# WS2811Controller.net
KiCad netlist of a schematic drawn in EAGLE
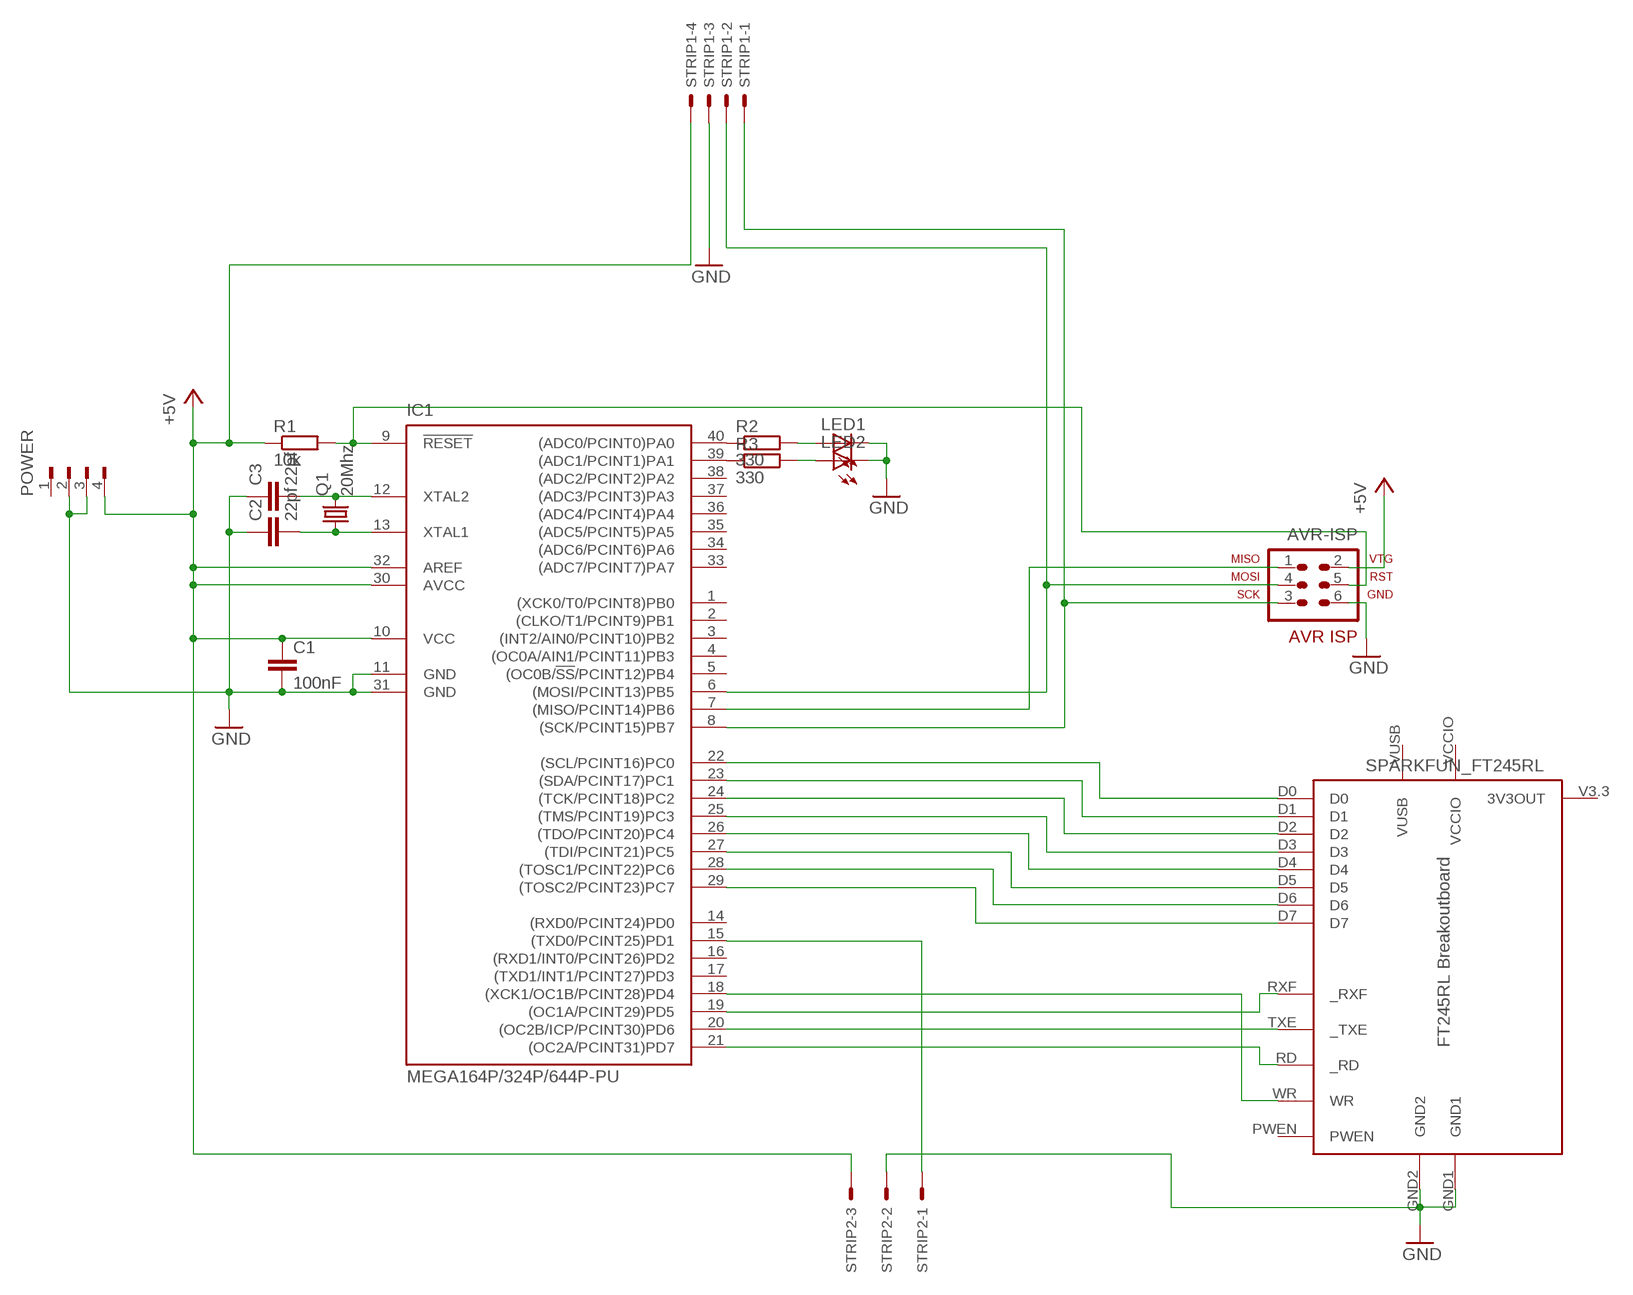
[diagram p0: schematic, sheet 1]

(export (version "E")
  (design (tool "Eeschema 10.0.6"))
  (components
    (comp (ref "AVR-ISP")
      (value "AVR-ISP-6")
      (footprint "eagle-import:AVR-ISP-6")
      (libsource (lib "eagle-import") (part "AVR-ISP-6"))
    )
    (comp (ref "C1")
      (value "100nF")
      (footprint "eagle-import:C050-030X075")
      (libsource (lib "eagle-import") (part "C-EU050-030X075"))
    )
    (comp (ref "C2")
      (value "22pf")
      (footprint "eagle-import:C050-024X044")
      (libsource (lib "eagle-import") (part "C-EU050-024X044"))
    )
    (comp (ref "C3")
      (value "22pf")
      (footprint "eagle-import:C050-024X044")
      (libsource (lib "eagle-import") (part "C-EU050-024X044"))
    )
    (comp (ref "IC1")
      (value "MEGA164P/324P/644P-PU")
      (footprint "eagle-import:DIL40")
      (libsource (lib "eagle-import") (part "MEGA164P/324P/644P-PU"))
    )
    (comp (ref "LED1")
      (value "LED3MM")
      (footprint "eagle-import:LED3MM")
      (libsource (lib "eagle-import") (part "LED3MM"))
    )
    (comp (ref "LED2")
      (value "LED3MM")
      (footprint "eagle-import:LED3MM")
      (libsource (lib "eagle-import") (part "LED3MM"))
    )
    (comp (ref "POWER")
      (value "FLOPPY-4901")
      (footprint "eagle-import:827001")
      (libsource (lib "eagle-import") (part "FLOPPY-4901"))
    )
    (comp (ref "Q1")
      (value "20Mhz")
      (footprint "eagle-import:HC49U70")
      (libsource (lib "eagle-import") (part "CRYSTALHC49U70"))
    )
    (comp (ref "R1")
      (value "10k")
      (footprint "eagle-import:0207_10")
      (libsource (lib "eagle-import") (part "R-EU_0207/10"))
    )
    (comp (ref "R2")
      (value "330")
      (footprint "eagle-import:0207_10")
      (libsource (lib "eagle-import") (part "R-EU_0207/10"))
    )
    (comp (ref "R3")
      (value "330")
      (footprint "eagle-import:0207_10")
      (libsource (lib "eagle-import") (part "R-EU_0207/10"))
    )
    (comp (ref "SPARKFUN_FT245RL")
      (value "FT245RL_BREAKOUTBOARD")
      (footprint "eagle-import:SPARKFUN_FT245RL_BOARD")
      (libsource (lib "eagle-import") (part "FT245RL_BREAKOUTBOARD"))
    )
    (comp (ref "STRIP1")
      (value "22-27-2041-04")
      (footprint "eagle-import:6410-04")
      (libsource (lib "eagle-import") (part "22-?-0427-2041"))
    )
    (comp (ref "STRIP2")
      (value "22-27-2031-03")
      (footprint "eagle-import:6410-03")
      (libsource (lib "eagle-import") (part "22-?-0327-2031"))
    )
  )
  (nets
    (net (code "1") (name "+5V") (class "Default")
      (node (ref "AVR-ISP") (pin "2") (pinfunction "2_2") (pintype "passive"))
      (node (ref "C1") (pin "1") (pinfunction "1_1") (pintype "passive"))
      (node (ref "IC1") (pin "10") (pinfunction "VCC_10") (pintype "power_in"))
      (node (ref "IC1") (pin "30") (pinfunction "AVCC_30") (pintype "power_in"))
      (node (ref "IC1") (pin "32") (pinfunction "AREF_32") (pintype "power_in"))
      (node (ref "POWER") (pin "4") (pinfunction "4_4") (pintype "passive"))
      (node (ref "R1") (pin "1") (pinfunction "1_1") (pintype "passive"))
      (node (ref "STRIP1") (pin "4") (pinfunction "S_4") (pintype "passive"))
      (node (ref "STRIP2") (pin "3") (pinfunction "S_3") (pintype "passive"))
    )
    (net (code "2") (name "/VCCIO") (class "Default")
      (node (ref "SPARKFUN_FT245RL") (pin "VCCIO") (pinfunction "VCCIO_VCCIO") (pintype "power_in"))
    )
    (net (code "3") (name "GND") (class "Default")
      (node (ref "AVR-ISP") (pin "6") (pinfunction "6_6") (pintype "passive"))
      (node (ref "C1") (pin "2") (pinfunction "2_2") (pintype "passive"))
      (node (ref "C2") (pin "1") (pinfunction "1_1") (pintype "passive"))
      (node (ref "C3") (pin "1") (pinfunction "1_1") (pintype "passive"))
      (node (ref "IC1") (pin "11") (pinfunction "GND_11") (pintype "power_in"))
      (node (ref "IC1") (pin "31") (pinfunction "GND_31") (pintype "power_in"))
      (node (ref "LED1") (pin "K") (pinfunction "C_K") (pintype "passive"))
      (node (ref "LED2") (pin "K") (pinfunction "C_K") (pintype "passive"))
      (node (ref "POWER") (pin "2") (pinfunction "2_2") (pintype "passive"))
      (node (ref "POWER") (pin "3") (pinfunction "3_3") (pintype "passive"))
      (node (ref "SPARKFUN_FT245RL") (pin "GND1") (pinfunction "GND1_GND1") (pintype "power_in"))
      (node (ref "SPARKFUN_FT245RL") (pin "GND2") (pinfunction "GND2_GND2") (pintype "power_in"))
      (node (ref "STRIP1") (pin "3") (pinfunction "S_3") (pintype "passive"))
      (node (ref "STRIP2") (pin "2") (pinfunction "S_2") (pintype "passive"))
    )
    (net (code "4") (name "Net-(IC1-(ADC0{slash}PCINT0)PA0)") (class "Default")
      (node (ref "IC1") (pin "40") (pinfunction "(ADC0/PCINT0)PA0_40") (pintype "bidirectional"))
      (node (ref "R2") (pin "1") (pinfunction "1_1") (pintype "passive"))
    )
    (net (code "5") (name "Net-(IC1-(ADC1{slash}PCINT1)PA1)") (class "Default")
      (node (ref "IC1") (pin "39") (pinfunction "(ADC1/PCINT1)PA1_39") (pintype "bidirectional"))
      (node (ref "R3") (pin "1") (pinfunction "1_1") (pintype "passive"))
    )
    (net (code "6") (name "Net-(IC1-(MISO{slash}PCINT14)PB6)") (class "Default")
      (node (ref "AVR-ISP") (pin "1") (pinfunction "1_1") (pintype "passive"))
      (node (ref "IC1") (pin "7") (pinfunction "(MISO/PCINT14)PB6_7") (pintype "bidirectional"))
    )
    (net (code "7") (name "Net-(IC1-(MOSI{slash}PCINT13)PB5)") (class "Default")
      (node (ref "AVR-ISP") (pin "4") (pinfunction "4_4") (pintype "passive"))
      (node (ref "IC1") (pin "6") (pinfunction "(MOSI/PCINT13)PB5_6") (pintype "bidirectional"))
      (node (ref "STRIP1") (pin "2") (pinfunction "S_2") (pintype "passive"))
    )
    (net (code "8") (name "Net-(IC1-(OC1A{slash}PCINT29)PD5)") (class "Default")
      (node (ref "IC1") (pin "19") (pinfunction "(OC1A/PCINT29)PD5_19") (pintype "bidirectional"))
      (node (ref "SPARKFUN_FT245RL") (pin "RXF") (pinfunction "_RXF_RXF") (pintype "bidirectional"))
    )
    (net (code "9") (name "Net-(IC1-(OC2A{slash}PCINT31)PD7)") (class "Default")
      (node (ref "IC1") (pin "21") (pinfunction "(OC2A/PCINT31)PD7_21") (pintype "bidirectional"))
      (node (ref "SPARKFUN_FT245RL") (pin "RD") (pinfunction "_RD_RD") (pintype "bidirectional"))
    )
    (net (code "10") (name "Net-(IC1-(OC2B{slash}ICP{slash}PCINT30)PD6)") (class "Default")
      (node (ref "IC1") (pin "20") (pinfunction "(OC2B/ICP/PCINT30)PD6_20") (pintype "bidirectional"))
      (node (ref "SPARKFUN_FT245RL") (pin "TXE") (pinfunction "_TXE_TXE") (pintype "bidirectional"))
    )
    (net (code "11") (name "Net-(IC1-(SCK{slash}PCINT15)PB7)") (class "Default")
      (node (ref "AVR-ISP") (pin "3") (pinfunction "3_3") (pintype "passive"))
      (node (ref "IC1") (pin "8") (pinfunction "(SCK/PCINT15)PB7_8") (pintype "bidirectional"))
      (node (ref "STRIP1") (pin "1") (pinfunction "S_1") (pintype "passive"))
    )
    (net (code "12") (name "Net-(IC1-(SCL{slash}PCINT16)PC0)") (class "Default")
      (node (ref "IC1") (pin "22") (pinfunction "(SCL/PCINT16)PC0_22") (pintype "bidirectional"))
      (node (ref "SPARKFUN_FT245RL") (pin "D0") (pinfunction "D0_D0") (pintype "output"))
    )
    (net (code "13") (name "Net-(IC1-(SDA{slash}PCINT17)PC1)") (class "Default")
      (node (ref "IC1") (pin "23") (pinfunction "(SDA/PCINT17)PC1_23") (pintype "bidirectional"))
      (node (ref "SPARKFUN_FT245RL") (pin "D1") (pinfunction "D1_D1") (pintype "input"))
    )
    (net (code "14") (name "Net-(IC1-(TCK{slash}PCINT18)PC2)") (class "Default")
      (node (ref "IC1") (pin "24") (pinfunction "(TCK/PCINT18)PC2_24") (pintype "bidirectional"))
      (node (ref "SPARKFUN_FT245RL") (pin "D2") (pinfunction "D2_D2") (pintype "output"))
    )
    (net (code "15") (name "Net-(IC1-(TDI{slash}PCINT21)PC5)") (class "Default")
      (node (ref "IC1") (pin "27") (pinfunction "(TDI/PCINT21)PC5_27") (pintype "bidirectional"))
      (node (ref "SPARKFUN_FT245RL") (pin "D5") (pinfunction "D5_D5") (pintype "input"))
    )
    (net (code "16") (name "Net-(IC1-(TDO{slash}PCINT20)PC4)") (class "Default")
      (node (ref "IC1") (pin "26") (pinfunction "(TDO/PCINT20)PC4_26") (pintype "bidirectional"))
      (node (ref "SPARKFUN_FT245RL") (pin "D4") (pinfunction "D4_D4") (pintype "output"))
    )
    (net (code "17") (name "Net-(IC1-(TMS{slash}PCINT19)PC3)") (class "Default")
      (node (ref "IC1") (pin "25") (pinfunction "(TMS/PCINT19)PC3_25") (pintype "bidirectional"))
      (node (ref "SPARKFUN_FT245RL") (pin "D3") (pinfunction "D3_D3") (pintype "input"))
    )
    (net (code "18") (name "Net-(IC1-(TOSC1{slash}PCINT22)PC6)") (class "Default")
      (node (ref "IC1") (pin "28") (pinfunction "(TOSC1/PCINT22)PC6_28") (pintype "bidirectional"))
      (node (ref "SPARKFUN_FT245RL") (pin "D6") (pinfunction "D6_D6") (pintype "input"))
    )
    (net (code "19") (name "Net-(IC1-(TOSC2{slash}PCINT23)PC7)") (class "Default")
      (node (ref "IC1") (pin "29") (pinfunction "(TOSC2/PCINT23)PC7_29") (pintype "bidirectional"))
      (node (ref "SPARKFUN_FT245RL") (pin "D7") (pinfunction "D7_D7") (pintype "input"))
    )
    (net (code "20") (name "Net-(IC1-(TXD0{slash}PCINT25)PD1)") (class "Default")
      (node (ref "IC1") (pin "15") (pinfunction "(TXD0/PCINT25)PD1_15") (pintype "bidirectional"))
      (node (ref "STRIP2") (pin "1") (pinfunction "S_1") (pintype "passive"))
    )
    (net (code "21") (name "Net-(IC1-(XCK1{slash}OC1B{slash}PCINT28)PD4)") (class "Default")
      (node (ref "IC1") (pin "18") (pinfunction "(XCK1/OC1B/PCINT28)PD4_18") (pintype "bidirectional"))
      (node (ref "SPARKFUN_FT245RL") (pin "WR") (pinfunction "WR_WR") (pintype "bidirectional"))
    )
    (net (code "22") (name "Net-(IC1-XTAL1)") (class "Default")
      (node (ref "C2") (pin "2") (pinfunction "2_2") (pintype "passive"))
      (node (ref "IC1") (pin "13") (pinfunction "XTAL1_13") (pintype "input"))
      (node (ref "Q1") (pin "1") (pinfunction "1_1") (pintype "passive"))
    )
    (net (code "23") (name "Net-(IC1-XTAL2)") (class "Default")
      (node (ref "C3") (pin "2") (pinfunction "2_2") (pintype "passive"))
      (node (ref "IC1") (pin "12") (pinfunction "XTAL2_12") (pintype "output"))
      (node (ref "Q1") (pin "2") (pinfunction "2_2") (pintype "passive"))
    )
    (net (code "24") (name "Net-(IC1-~{RESET})") (class "Default")
      (node (ref "AVR-ISP") (pin "5") (pinfunction "5_5") (pintype "passive"))
      (node (ref "IC1") (pin "9") (pinfunction "~{RESET}_9") (pintype "input"))
      (node (ref "R1") (pin "2") (pinfunction "2_2") (pintype "passive"))
    )
    (net (code "25") (name "Net-(LED1-PadA)") (class "Default")
      (node (ref "LED1") (pin "A") (pinfunction "A_A") (pintype "passive"))
      (node (ref "R2") (pin "2") (pinfunction "2_2") (pintype "passive"))
    )
    (net (code "26") (name "Net-(LED2-PadA)") (class "Default")
      (node (ref "LED2") (pin "A") (pinfunction "A_A") (pintype "passive"))
      (node (ref "R3") (pin "2") (pinfunction "2_2") (pintype "passive"))
    )
    (net (code "27") (name "unconnected-(IC1-(ADC2{slash}PCINT2)PA2-Pad38)") (class "Default")
      (node (ref "IC1") (pin "38") (pinfunction "(ADC2/PCINT2)PA2_38") (pintype "bidirectional"))
    )
    (net (code "28") (name "unconnected-(IC1-(ADC3{slash}PCINT3)PA3-Pad37)") (class "Default")
      (node (ref "IC1") (pin "37") (pinfunction "(ADC3/PCINT3)PA3_37") (pintype "bidirectional"))
    )
    (net (code "29") (name "unconnected-(IC1-(ADC4{slash}PCINT4)PA4-Pad36)") (class "Default")
      (node (ref "IC1") (pin "36") (pinfunction "(ADC4/PCINT4)PA4_36") (pintype "bidirectional"))
    )
    (net (code "30") (name "unconnected-(IC1-(ADC5{slash}PCINT5)PA5-Pad35)") (class "Default")
      (node (ref "IC1") (pin "35") (pinfunction "(ADC5/PCINT5)PA5_35") (pintype "bidirectional"))
    )
    (net (code "31") (name "unconnected-(IC1-(ADC6{slash}PCINT6)PA6-Pad34)") (class "Default")
      (node (ref "IC1") (pin "34") (pinfunction "(ADC6/PCINT6)PA6_34") (pintype "bidirectional"))
    )
    (net (code "32") (name "unconnected-(IC1-(ADC7{slash}PCINT7)PA7-Pad33)") (class "Default")
      (node (ref "IC1") (pin "33") (pinfunction "(ADC7/PCINT7)PA7_33") (pintype "bidirectional"))
    )
    (net (code "33") (name "unconnected-(IC1-(CLKO{slash}T1{slash}PCINT9)PB1-Pad2)") (class "Default")
      (node (ref "IC1") (pin "2") (pinfunction "(CLKO/T1/PCINT9)PB1_2") (pintype "bidirectional"))
    )
    (net (code "34") (name "unconnected-(IC1-(INT2{slash}AIN0{slash}PCINT10)PB2-Pad3)") (class "Default")
      (node (ref "IC1") (pin "3") (pinfunction "(INT2/AIN0/PCINT10)PB2_3") (pintype "bidirectional"))
    )
    (net (code "35") (name "unconnected-(IC1-(OC0A{slash}AIN1{slash}PCINT11)PB3-Pad4)") (class "Default")
      (node (ref "IC1") (pin "4") (pinfunction "(OC0A/AIN1/PCINT11)PB3_4") (pintype "bidirectional"))
    )
    (net (code "36") (name "unconnected-(IC1-(OC0B{slash}~{SS}{slash}PCINT12)PB4-Pad5)") (class "Default")
      (node (ref "IC1") (pin "5") (pinfunction "(OC0B/~{SS}/PCINT12)PB4_5") (pintype "bidirectional"))
    )
    (net (code "37") (name "unconnected-(IC1-(RXD0{slash}PCINT24)PD0-Pad14)") (class "Default")
      (node (ref "IC1") (pin "14") (pinfunction "(RXD0/PCINT24)PD0_14") (pintype "bidirectional"))
    )
    (net (code "38") (name "unconnected-(IC1-(RXD1{slash}INT0{slash}PCINT26)PD2-Pad16)") (class "Default")
      (node (ref "IC1") (pin "16") (pinfunction "(RXD1/INT0/PCINT26)PD2_16") (pintype "bidirectional"))
    )
    (net (code "39") (name "unconnected-(IC1-(TXD1{slash}INT1{slash}PCINT27)PD3-Pad17)") (class "Default")
      (node (ref "IC1") (pin "17") (pinfunction "(TXD1/INT1/PCINT27)PD3_17") (pintype "bidirectional"))
    )
    (net (code "40") (name "unconnected-(IC1-(XCK0{slash}T0{slash}PCINT8)PB0-Pad1)") (class "Default")
      (node (ref "IC1") (pin "1") (pinfunction "(XCK0/T0/PCINT8)PB0_1") (pintype "bidirectional"))
    )
    (net (code "41") (name "unconnected-(POWER-Pad1)") (class "Default")
      (node (ref "POWER") (pin "1") (pinfunction "1_1") (pintype "passive"))
    )
    (net (code "42") (name "unconnected-(SPARKFUN_FT245RL-3V3OUT-PadV3.3)") (class "Default")
      (node (ref "SPARKFUN_FT245RL") (pin "V3.3") (pinfunction "3V3OUT_V3.3") (pintype "output"))
    )
    (net (code "43") (name "unconnected-(SPARKFUN_FT245RL-PadPWEN)") (class "Default")
      (node (ref "SPARKFUN_FT245RL") (pin "PWEN") (pinfunction "PWEN_PWEN") (pintype "bidirectional"))
    )
    (net (code "44") (name "unconnected-(SPARKFUN_FT245RL-PadVUSB)") (class "Default")
      (node (ref "SPARKFUN_FT245RL") (pin "VUSB") (pinfunction "VUSB_VUSB") (pintype "bidirectional"))
    )
  )
)
